# Ethernet.net
KiCad netlist of a schematic drawn in Altium Designer
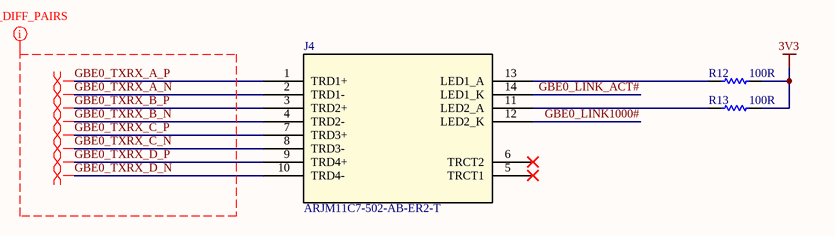
[diagram p0: Ethernet.SchDoc]

(export (version "E")
  (design (tool "Eeschema 10.0.6"))
  (components
    (comp (ref "J4")
      (value "ARJM11C7-502-AB-ER2-T")
      (footprint "ARJM11C7-502-AB-ER2-T_ABR")
      (description "Ethernet connector with magnetics (1000-T Base)")
      (fields (field (name "COPYRIGHT") "Copyright (C) 2025 Ultra Librarian. All rights reserved."))
      (libsource (lib "Master") (part "ARJM11C7-502-AB-ER2-T"))
    )
    (comp (ref "R12")
      (value "100R")
      (footprint "RES-0603")
      (description "Resistor chip. 0603")
      (libsource (lib "Master") (part "RES-0603"))
    )
    (comp (ref "R13")
      (value "100R")
      (footprint "RES-0603")
      (description "Resistor chip. 0603")
      (libsource (lib "Master") (part "RES-0603"))
    )
  )
  (nets
    (net (code "1") (name "/GBE0_LINK1000#") (class "Default")
      (node (ref "J4") (pin "12") (pinfunction "LED2_K_12") (pintype "passive"))
    )
    (net (code "2") (name "/GBE0_LINK_ACT#") (class "Default")
      (node (ref "J4") (pin "14") (pinfunction "LED1_K_14") (pintype "passive"))
    )
    (net (code "3") (name "/GBE0_TXRX_A_N") (class "Default")
      (node (ref "J4") (pin "2") (pinfunction "TRD1-_2") (pintype "passive"))
    )
    (net (code "4") (name "/GBE0_TXRX_A_P") (class "Default")
      (node (ref "J4") (pin "1") (pinfunction "TRD1+_1") (pintype "passive"))
    )
    (net (code "5") (name "/GBE0_TXRX_B_N") (class "Default")
      (node (ref "J4") (pin "4") (pinfunction "TRD2-_4") (pintype "passive"))
    )
    (net (code "6") (name "/GBE0_TXRX_B_P") (class "Default")
      (node (ref "J4") (pin "3") (pinfunction "TRD2+_3") (pintype "passive"))
    )
    (net (code "7") (name "/GBE0_TXRX_C_N") (class "Default")
      (node (ref "J4") (pin "8") (pinfunction "TRD3-_8") (pintype "passive"))
    )
    (net (code "8") (name "/GBE0_TXRX_C_P") (class "Default")
      (node (ref "J4") (pin "7") (pinfunction "TRD3+_7") (pintype "passive"))
    )
    (net (code "9") (name "/GBE0_TXRX_D_N") (class "Default")
      (node (ref "J4") (pin "10") (pinfunction "TRD4-_10") (pintype "passive"))
    )
    (net (code "10") (name "/GBE0_TXRX_D_P") (class "Default")
      (node (ref "J4") (pin "9") (pinfunction "TRD4+_9") (pintype "passive"))
    )
    (net (code "11") (name "3V3") (class "Default")
      (node (ref "R12") (pin "2") (pintype "passive"))
      (node (ref "R13") (pin "2") (pintype "passive"))
    )
    (net (code "12") (name "Net-(J4-LED1_A)") (class "Default")
      (node (ref "J4") (pin "13") (pinfunction "LED1_A_13") (pintype "passive"))
      (node (ref "R12") (pin "1") (pintype "passive"))
    )
    (net (code "13") (name "Net-(J4-LED2_A)") (class "Default")
      (node (ref "J4") (pin "11") (pinfunction "LED2_A_11") (pintype "passive"))
      (node (ref "R13") (pin "1") (pintype "passive"))
    )
    (net (code "14") (name "unconnected-(J4-TRCT1-Pad5)") (class "Default")
      (node (ref "J4") (pin "5") (pinfunction "TRCT1_5") (pintype "passive+no_connect"))
    )
    (net (code "15") (name "unconnected-(J4-TRCT2-Pad6)") (class "Default")
      (node (ref "J4") (pin "6") (pinfunction "TRCT2_6") (pintype "passive+no_connect"))
    )
  )
)
